# test_shield.net
KiCad netlist of a schematic drawn in EAGLE
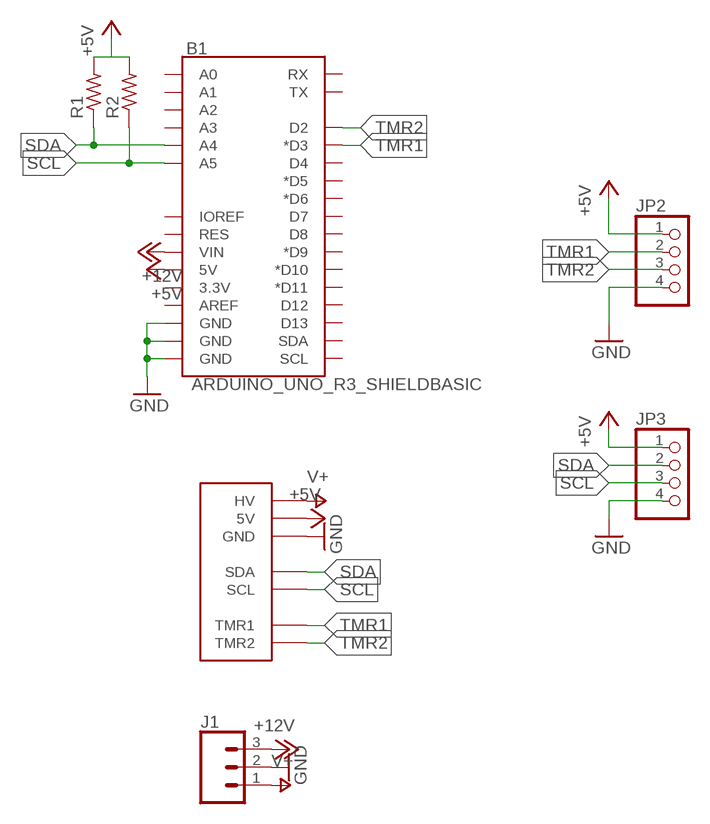
[diagram p0: schematic, sheet 1]

(export (version "E")
  (design (tool "Eeschema 10.0.6"))
  (components
    (comp (ref "B1")
      (value "ARDUINO_UNO_R3_SHIELDBASIC")
      (footprint "eagle-import:UNO_R3_SHIELD")
      (libsource (lib "eagle-import") (part "ARDUINO_UNO_R3_SHIELDBASIC"))
    )
    (comp (ref "J1")
      (value "CONN_03-SCREW-5MM")
      (footprint "eagle-import:SCREWTERMINAL-5MM-3")
      (libsource (lib "eagle-import") (part "CONN_03-SCREW-5MM"))
    )
    (comp (ref "JP1")
      (value "PCIE_RA")
      (footprint "eagle-import:PCIE_RA")
      (libsource (lib "eagle-import") (part "PCIE_RA"))
    )
    (comp (ref "JP2")
      (value "PINHD-1X4")
      (footprint "eagle-import:1X04")
      (libsource (lib "eagle-import") (part "PINHD-1X4"))
    )
    (comp (ref "JP3")
      (value "PINHD-1X4")
      (footprint "eagle-import:1X04")
      (libsource (lib "eagle-import") (part "PINHD-1X4"))
    )
    (comp (ref "R1")
      (value "R-US_0207/10")
      (footprint "eagle-import:0207_10")
      (libsource (lib "eagle-import") (part "R-US_0207/10"))
    )
    (comp (ref "R2")
      (value "R-US_0207/10")
      (footprint "eagle-import:0207_10")
      (libsource (lib "eagle-import") (part "R-US_0207/10"))
    )
  )
  (nets
    (net (code "1") (name "+5V") (class "Default")
      (node (ref "B1") (pin "5V") (pinfunction "5V_5V") (pintype "bidirectional"))
      (node (ref "JP1") (pin "A12") (pinfunction "5V_A12") (pintype "passive"))
      (node (ref "JP1") (pin "A13") (pinfunction "5V_A13") (pintype "passive"))
      (node (ref "JP1") (pin "A14") (pinfunction "5V_A14") (pintype "passive"))
      (node (ref "JP1") (pin "B12") (pinfunction "5V_B12") (pintype "passive"))
      (node (ref "JP1") (pin "B13") (pinfunction "5V_B13") (pintype "passive"))
      (node (ref "JP1") (pin "B14") (pinfunction "5V_B14") (pintype "passive"))
      (node (ref "JP2") (pin "1") (pinfunction "1_1") (pintype "passive"))
      (node (ref "JP3") (pin "1") (pinfunction "1_1") (pintype "passive"))
      (node (ref "R1") (pin "2") (pinfunction "2_2") (pintype "passive"))
      (node (ref "R2") (pin "2") (pinfunction "2_2") (pintype "passive"))
    )
    (net (code "2") (name "+12V") (class "Default")
      (node (ref "B1") (pin "VIN") (pinfunction "VIN_VIN") (pintype "bidirectional"))
      (node (ref "J1") (pin "3") (pinfunction "3_3") (pintype "passive"))
    )
    (net (code "3") (name "GND") (class "Default")
      (node (ref "B1") (pin "GND@0") (pinfunction "GND_GND@0") (pintype "bidirectional"))
      (node (ref "B1") (pin "GND@1") (pinfunction "GND_GND@1") (pintype "bidirectional"))
      (node (ref "B1") (pin "GND@2") (pinfunction "GND_GND@2") (pintype "bidirectional"))
      (node (ref "J1") (pin "2") (pinfunction "2_2") (pintype "passive"))
      (node (ref "JP1") (pin "A1") (pinfunction "GND_A1") (pintype "passive"))
      (node (ref "JP1") (pin "A2") (pinfunction "GND_A2") (pintype "passive"))
      (node (ref "JP1") (pin "A3") (pinfunction "GND_A3") (pintype "passive"))
      (node (ref "JP1") (pin "B1") (pinfunction "GND_B1") (pintype "passive"))
      (node (ref "JP1") (pin "B2") (pinfunction "GND_B2") (pintype "passive"))
      (node (ref "JP1") (pin "B3") (pinfunction "GND_B3") (pintype "passive"))
      (node (ref "JP2") (pin "4") (pinfunction "4_4") (pintype "passive"))
      (node (ref "JP3") (pin "4") (pinfunction "4_4") (pintype "passive"))
    )
    (net (code "4") (name "SCL") (class "Default")
      (node (ref "B1") (pin "A5") (pinfunction "A5_A5") (pintype "bidirectional"))
      (node (ref "JP1") (pin "A5") (pinfunction "SCL_A5") (pintype "bidirectional"))
      (node (ref "JP1") (pin "B5") (pinfunction "SCL_B5") (pintype "bidirectional"))
      (node (ref "JP3") (pin "3") (pinfunction "3_3") (pintype "passive"))
      (node (ref "R2") (pin "1") (pinfunction "1_1") (pintype "passive"))
    )
    (net (code "5") (name "SDA") (class "Default")
      (node (ref "B1") (pin "A4") (pinfunction "A4_A4") (pintype "bidirectional"))
      (node (ref "JP1") (pin "A6") (pinfunction "SDA_A6") (pintype "bidirectional"))
      (node (ref "JP1") (pin "B6") (pinfunction "SDA_B6") (pintype "bidirectional"))
      (node (ref "JP3") (pin "2") (pinfunction "2_2") (pintype "passive"))
      (node (ref "R1") (pin "1") (pinfunction "1_1") (pintype "passive"))
    )
    (net (code "6") (name "TMR1") (class "Default")
      (node (ref "B1") (pin "D3") (pinfunction "*D3_D3") (pintype "bidirectional"))
      (node (ref "JP1") (pin "A8") (pinfunction "TMR1_A8") (pintype "bidirectional"))
      (node (ref "JP1") (pin "B8") (pinfunction "TMR1_B8") (pintype "bidirectional"))
      (node (ref "JP2") (pin "2") (pinfunction "2_2") (pintype "passive"))
    )
    (net (code "7") (name "TMR2") (class "Default")
      (node (ref "B1") (pin "D2") (pinfunction "D2_D2") (pintype "bidirectional"))
      (node (ref "JP1") (pin "A9") (pinfunction "TMR2_A9") (pintype "bidirectional"))
      (node (ref "JP1") (pin "B9") (pinfunction "TMR2_B9") (pintype "bidirectional"))
      (node (ref "JP2") (pin "3") (pinfunction "3_3") (pintype "passive"))
    )
    (net (code "8") (name "V+") (class "Default")
      (node (ref "J1") (pin "1") (pinfunction "1_1") (pintype "passive"))
      (node (ref "JP1") (pin "A16") (pinfunction "HV_A16") (pintype "passive"))
      (node (ref "JP1") (pin "A17") (pinfunction "HV_A17") (pintype "passive"))
      (node (ref "JP1") (pin "A18") (pinfunction "HV_A18") (pintype "passive"))
      (node (ref "JP1") (pin "B16") (pinfunction "HV_B16") (pintype "passive"))
      (node (ref "JP1") (pin "B17") (pinfunction "HV_B17") (pintype "passive"))
      (node (ref "JP1") (pin "B18") (pinfunction "HV_B18") (pintype "passive"))
    )
    (net (code "9") (name "unconnected-(B1-*D5-PadD5)") (class "Default")
      (node (ref "B1") (pin "D5") (pinfunction "*D5_D5") (pintype "bidirectional"))
    )
    (net (code "10") (name "unconnected-(B1-*D6-PadD6)") (class "Default")
      (node (ref "B1") (pin "D6") (pinfunction "*D6_D6") (pintype "bidirectional"))
    )
    (net (code "11") (name "unconnected-(B1-*D9-PadD9)") (class "Default")
      (node (ref "B1") (pin "D9") (pinfunction "*D9_D9") (pintype "bidirectional"))
    )
    (net (code "12") (name "unconnected-(B1-*D10-PadD10)") (class "Default")
      (node (ref "B1") (pin "D10") (pinfunction "*D10_D10") (pintype "bidirectional"))
    )
    (net (code "13") (name "unconnected-(B1-*D11-PadD11)") (class "Default")
      (node (ref "B1") (pin "D11") (pinfunction "*D11_D11") (pintype "bidirectional"))
    )
    (net (code "14") (name "unconnected-(B1-Pad3.3V)") (class "Default")
      (node (ref "B1") (pin "3.3V") (pinfunction "3.3V_3.3V") (pintype "bidirectional"))
    )
    (net (code "15") (name "unconnected-(B1-PadA0)") (class "Default")
      (node (ref "B1") (pin "A0") (pinfunction "A0_A0") (pintype "bidirectional"))
    )
    (net (code "16") (name "unconnected-(B1-PadA1)") (class "Default")
      (node (ref "B1") (pin "A1") (pinfunction "A1_A1") (pintype "bidirectional"))
    )
    (net (code "17") (name "unconnected-(B1-PadA2)") (class "Default")
      (node (ref "B1") (pin "A2") (pinfunction "A2_A2") (pintype "bidirectional"))
    )
    (net (code "18") (name "unconnected-(B1-PadA3)") (class "Default")
      (node (ref "B1") (pin "A3") (pinfunction "A3_A3") (pintype "bidirectional"))
    )
    (net (code "19") (name "unconnected-(B1-PadAREF)") (class "Default")
      (node (ref "B1") (pin "AREF") (pinfunction "AREF_AREF") (pintype "bidirectional"))
    )
    (net (code "20") (name "unconnected-(B1-PadD4)") (class "Default")
      (node (ref "B1") (pin "D4") (pinfunction "D4_D4") (pintype "bidirectional"))
    )
    (net (code "21") (name "unconnected-(B1-PadD7)") (class "Default")
      (node (ref "B1") (pin "D7") (pinfunction "D7_D7") (pintype "bidirectional"))
    )
    (net (code "22") (name "unconnected-(B1-PadD8)") (class "Default")
      (node (ref "B1") (pin "D8") (pinfunction "D8_D8") (pintype "bidirectional"))
    )
    (net (code "23") (name "unconnected-(B1-PadD12)") (class "Default")
      (node (ref "B1") (pin "D12") (pinfunction "D12_D12") (pintype "bidirectional"))
    )
    (net (code "24") (name "unconnected-(B1-PadD13)") (class "Default")
      (node (ref "B1") (pin "D13") (pinfunction "D13_D13") (pintype "bidirectional"))
    )
    (net (code "25") (name "unconnected-(B1-PadIOREF)") (class "Default")
      (node (ref "B1") (pin "IOREF") (pinfunction "IOREF_IOREF") (pintype "bidirectional"))
    )
    (net (code "26") (name "unconnected-(B1-PadRES)") (class "Default")
      (node (ref "B1") (pin "RES") (pinfunction "RES_RES") (pintype "bidirectional"))
    )
    (net (code "27") (name "unconnected-(B1-PadRX)") (class "Default")
      (node (ref "B1") (pin "RX") (pinfunction "RX_RX") (pintype "bidirectional"))
    )
    (net (code "28") (name "unconnected-(B1-PadSCL)") (class "Default")
      (node (ref "B1") (pin "SCL") (pinfunction "SCL_SCL") (pintype "bidirectional"))
    )
    (net (code "29") (name "unconnected-(B1-PadSDA)") (class "Default")
      (node (ref "B1") (pin "SDA") (pinfunction "SDA_SDA") (pintype "bidirectional"))
    )
    (net (code "30") (name "unconnected-(B1-PadTX)") (class "Default")
      (node (ref "B1") (pin "TX") (pinfunction "TX_TX") (pintype "bidirectional"))
    )
  )
)
